# STC12C5A60S2.net
KiCad netlist of a schematic drawn in Altium Designer
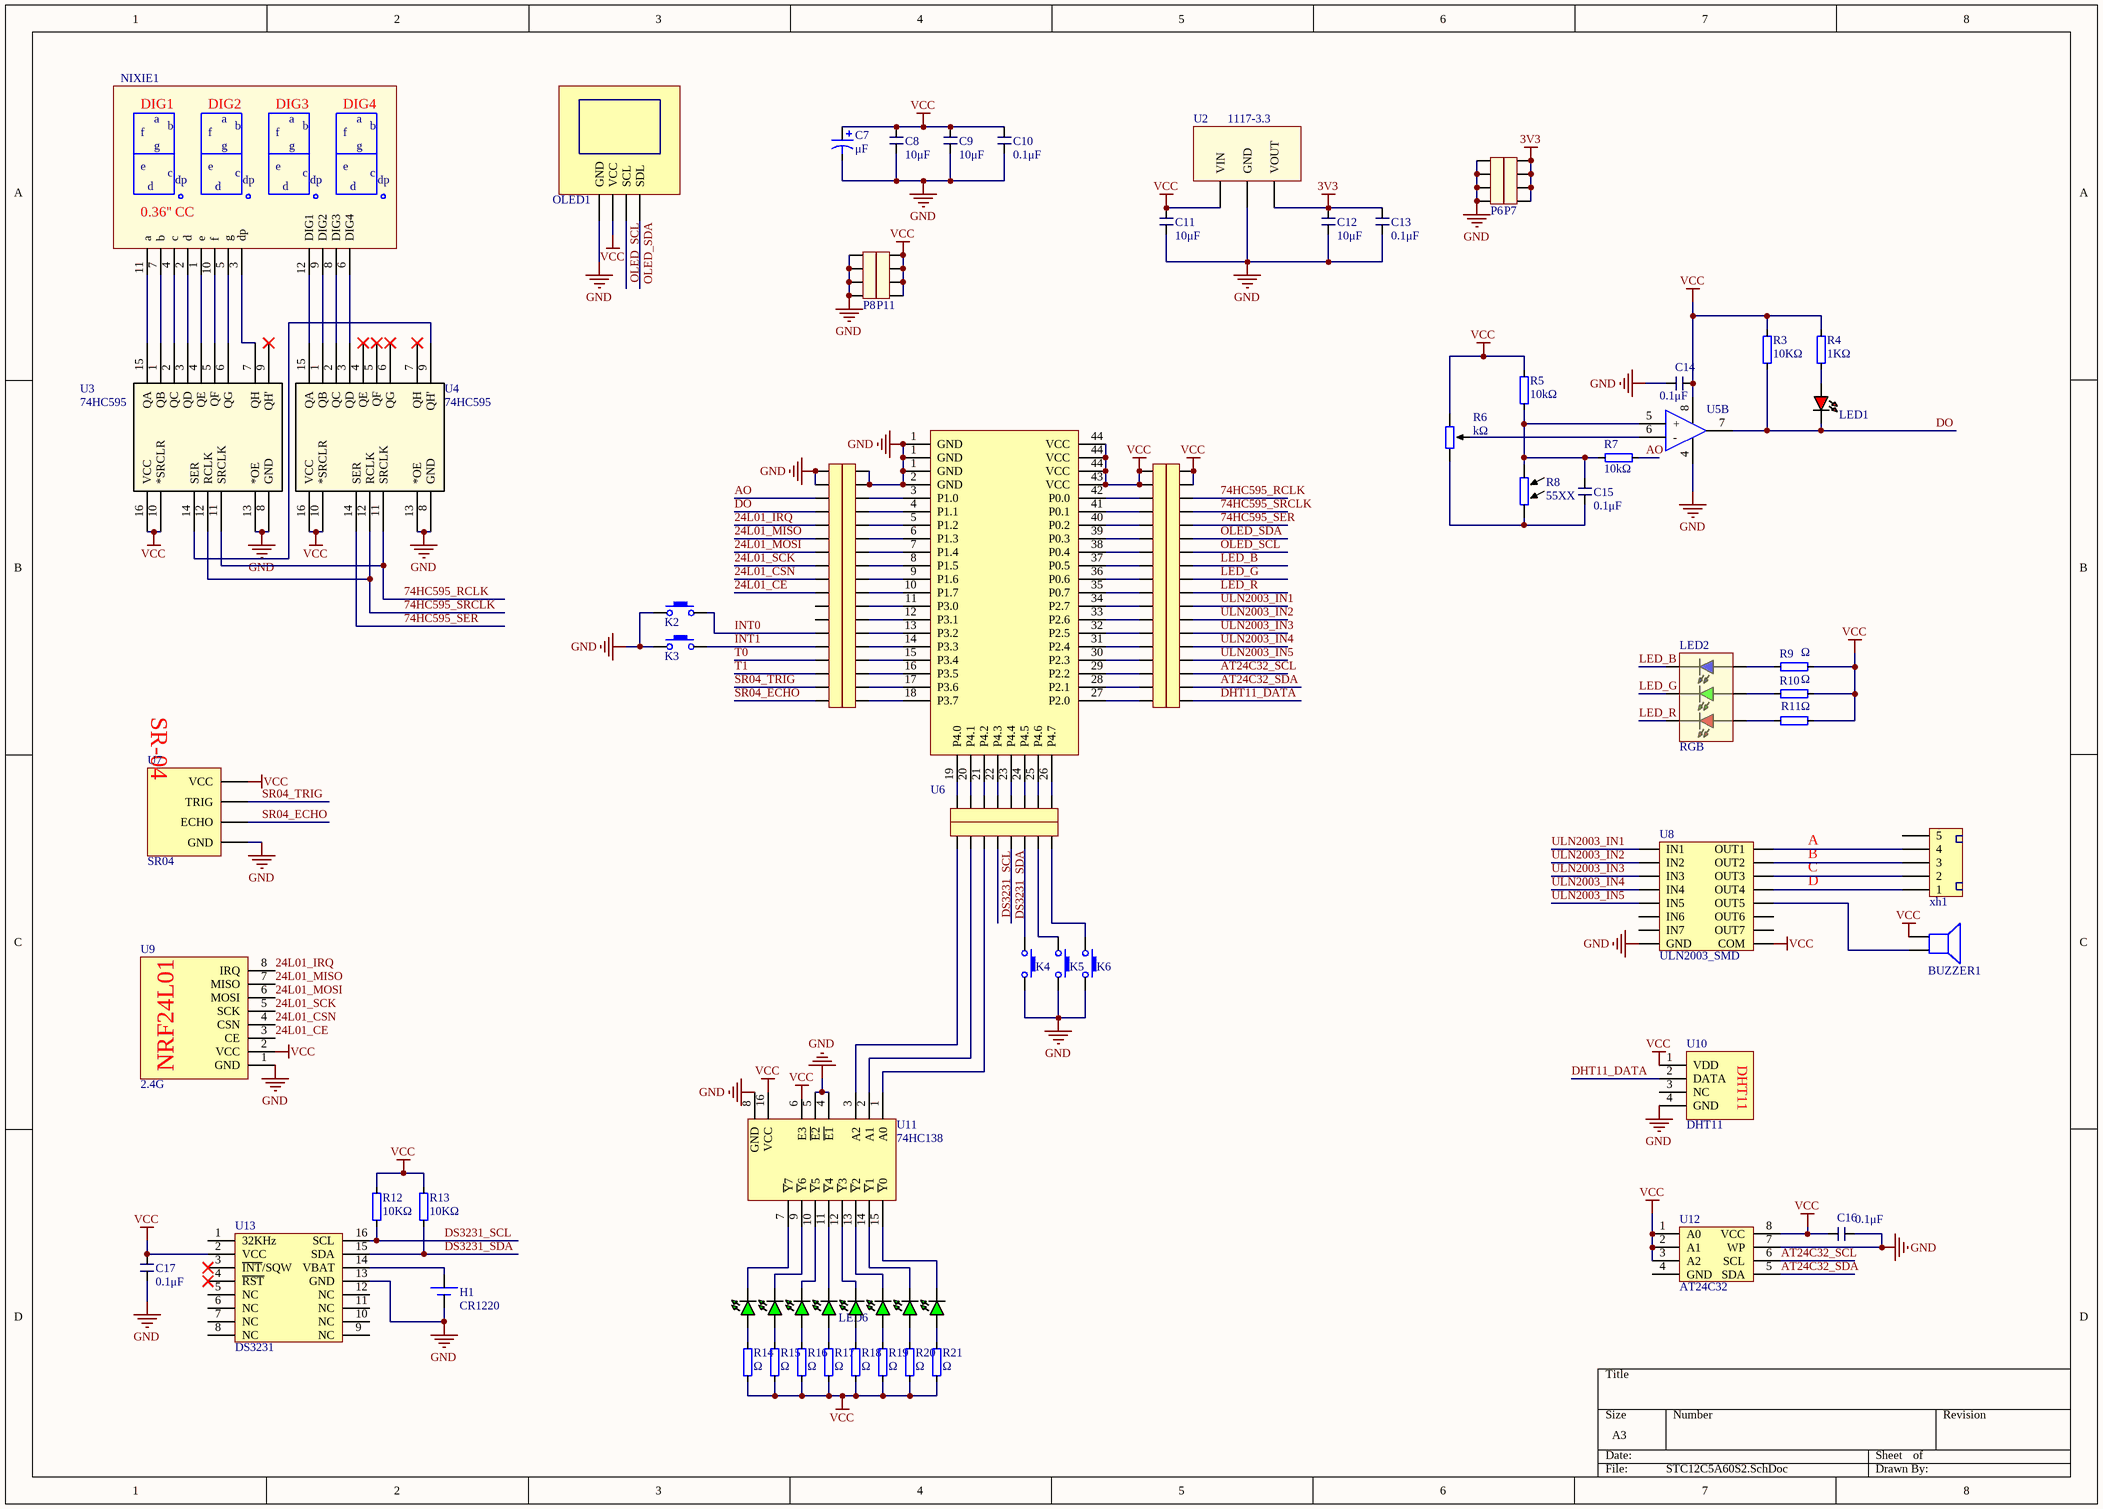
[diagram p0: STC12C5A60S2.SchDoc]

(export (version "E")
  (design (tool "Eeschema 10.0.6"))
  (components
    (comp (ref "BUZZER1")
      (value "BUZZER 9.6X5.5_4MM")
      (footprint "BUZZER9.6x4_4mm")
      (libsource (lib "节能库") (part "BUZZER 9.6X5.5_4MM"))
    )
    (comp (ref "C7") (value "μF") (footprint "TAC_C") (libsource (lib "节能库") (part "C_TAC-C")))
    (comp (ref "C8") (value "10μF") (footprint "C_0805") (libsource (lib "节能库") (part "C_0805")))
    (comp (ref "C9") (value "10μF") (footprint "C_0805") (libsource (lib "节能库") (part "C_0805")))
    (comp (ref "C10") (value "0.1μF") (footprint "C_0805") (libsource (lib "节能库") (part "C_0805")))
    (comp (ref "C11") (value "10μF") (footprint "C_0805") (libsource (lib "节能库") (part "C_0805")))
    (comp (ref "C12") (value "10μF") (footprint "C_0805") (libsource (lib "节能库") (part "C_0805")))
    (comp (ref "C13") (value "0.1μF") (footprint "C_0805") (libsource (lib "节能库") (part "C_0805")))
    (comp (ref "C14") (value "0.1μF") (footprint "C_0805") (libsource (lib "节能库") (part "C_0805")))
    (comp (ref "C15") (value "0.1μF") (footprint "C_0805") (libsource (lib "节能库") (part "C_0805")))
    (comp (ref "C16") (value "0.1μF") (footprint "C_0805") (libsource (lib "节能库") (part "C_0805")))
    (comp (ref "C17") (value "0.1μF") (footprint "C_0805") (libsource (lib "节能库") (part "C_0805")))
    (comp (ref "H1")
      (value "CR1220")
      (footprint "holder_CR1220_SMD")
      (libsource (lib "节能库") (part "holder_CR1220_SMD"))
    )
    (comp (ref "K2")
      (value "TACT SWITCH_4_DIP")
      (footprint "TACT SWITCH_4_DIP")
      (libsource (lib "") (part "TACT SWITCH_4_DIP_1"))
    )
    (comp (ref "K3")
      (value "TACT SWITCH_4_DIP")
      (footprint "TACT SWITCH_4_DIP")
      (libsource (lib "") (part "TACT SWITCH_4_DIP_1"))
    )
    (comp (ref "K4")
      (value "TACT SWITCH_4_DIP")
      (footprint "TACT SWITCH_4_DIP")
      (libsource (lib "节能库") (part "TACT SWITCH_4_DIP"))
    )
    (comp (ref "K5")
      (value "TACT SWITCH_4_DIP")
      (footprint "TACT SWITCH_4_DIP")
      (libsource (lib "节能库") (part "TACT SWITCH_4_DIP"))
    )
    (comp (ref "K6")
      (value "TACT SWITCH_4_DIP")
      (footprint "TACT SWITCH_4_DIP")
      (libsource (lib "节能库") (part "TACT SWITCH_4_DIP"))
    )
    (comp (ref "LED1")
      (value "LED_0603-R")
      (footprint "LED_0603-R")
      (libsource (lib "节能库") (part "LED_0603-R"))
    )
    (comp (ref "LED2") (value "RGB") (footprint "LED 5050_RGB") (libsource (lib "节能库") (part "LED_5050_RGB")))
    (comp (ref "LED3")
      (value "LED_0603-G")
      (footprint "LED_0603-G")
      (libsource (lib "节能库") (part "LED_0603-G"))
    )
    (comp (ref "LED4")
      (value "LED_0603-G")
      (footprint "LED_0603-G")
      (libsource (lib "节能库") (part "LED_0603-G"))
    )
    (comp (ref "LED5")
      (value "LED_0603-G")
      (footprint "LED_0603-G")
      (libsource (lib "节能库") (part "LED_0603-G"))
    )
    (comp (ref "LED6")
      (value "LED_0603-G")
      (footprint "LED_0603-G")
      (libsource (lib "节能库") (part "LED_0603-G"))
    )
    (comp (ref "LED7")
      (value "LED_0603-G")
      (footprint "LED_0603-G")
      (libsource (lib "节能库") (part "LED_0603-G"))
    )
    (comp (ref "LED8")
      (value "LED_0603-G")
      (footprint "LED_0603-G")
      (libsource (lib "节能库") (part "LED_0603-G"))
    )
    (comp (ref "LED9")
      (value "LED_0603-G")
      (footprint "LED_0603-G")
      (libsource (lib "节能库") (part "LED_0603-G"))
    )
    (comp (ref "LED10")
      (value "LED_0603-G")
      (footprint "LED_0603-G")
      (libsource (lib "节能库") (part "LED_0603-G"))
    )
    (comp (ref "NIXIE1")
      (value "Nixie Tube_CC(0.36in)_4")
      (footprint "Nixie Tube_4(0.36in)")
      (libsource (lib "节能库") (part "Nixie Tube_CC(0.36in)_4"))
    )
    (comp (ref "OLED1")
      (value "0.96''")
      (footprint "OLED 0.96''")
      (libsource (lib "节能库") (part "OLED 0.96''_module"))
    )
    (comp (ref "P6") (value "PIN4") (footprint "PIN_4") (libsource (lib "") (part "PIN4_1")))
    (comp (ref "P7") (value "PIN4") (footprint "PIN_4") (libsource (lib "节能库") (part "PIN4")))
    (comp (ref "P8") (value "PIN4") (footprint "PIN_4") (libsource (lib "") (part "PIN4_1")))
    (comp (ref "P11") (value "PIN4") (footprint "PIN_4") (libsource (lib "节能库") (part "PIN4")))
    (comp (ref "P12") (value "PIN8") (footprint "PIN_8") (libsource (lib "") (part "PIN8_1")))
    (comp (ref "P13") (value "PIN8") (footprint "PIN_8") (libsource (lib "节能库") (part "PIN8")))
    (comp (ref "PIN1") (value "PIN18") (footprint "PIN_18") (libsource (lib "") (part "PIN18_1")))
    (comp (ref "PIN2") (value "PIN18") (footprint "PIN_18") (libsource (lib "节能库") (part "PIN18")))
    (comp (ref "PIN3") (value "PIN18") (footprint "PIN_18") (libsource (lib "") (part "PIN18_1")))
    (comp (ref "PIN4") (value "PIN18") (footprint "PIN_18") (libsource (lib "节能库") (part "PIN18")))
    (comp (ref "R3") (value "10KΩ") (footprint "R_0805") (libsource (lib "节能库") (part "R_0805")))
    (comp (ref "R4") (value "1KΩ") (footprint "R_0805") (libsource (lib "节能库") (part "R_0805")))
    (comp (ref "R5") (value "10kΩ") (footprint "R_0805") (libsource (lib "节能库") (part "R_0805")))
    (comp (ref "R6") (value "kΩ") (footprint "RP_3362P") (libsource (lib "节能库") (part "RP_3362P")))
    (comp (ref "R7") (value "10kΩ") (footprint "R_0805") (libsource (lib "节能库") (part "R_0805")))
    (comp (ref "R8") (value "55XX") (footprint "GM55-55XX") (libsource (lib "节能库") (part "GM55-55XX")))
    (comp (ref "R9") (value "Ω") (footprint "R_0805") (libsource (lib "节能库") (part "R_0805")))
    (comp (ref "R10") (value "Ω") (footprint "R_0805") (libsource (lib "节能库") (part "R_0805")))
    (comp (ref "R11") (value "Ω") (footprint "R_0805") (libsource (lib "节能库") (part "R_0805")))
    (comp (ref "R12") (value "10KΩ") (footprint "R_0805") (libsource (lib "节能库") (part "R_0805")))
    (comp (ref "R13") (value "10KΩ") (footprint "R_0805") (libsource (lib "节能库") (part "R_0805")))
    (comp (ref "R14") (value "Ω") (footprint "R_0805") (libsource (lib "节能库") (part "R_0805")))
    (comp (ref "R15") (value "Ω") (footprint "R_0805") (libsource (lib "节能库") (part "R_0805")))
    (comp (ref "R16") (value "Ω") (footprint "R_0805") (libsource (lib "节能库") (part "R_0805")))
    (comp (ref "R17") (value "Ω") (footprint "R_0805") (libsource (lib "节能库") (part "R_0805")))
    (comp (ref "R18") (value "Ω") (footprint "R_0805") (libsource (lib "节能库") (part "R_0805")))
    (comp (ref "R19") (value "Ω") (footprint "R_0805") (libsource (lib "节能库") (part "R_0805")))
    (comp (ref "R20") (value "Ω") (footprint "R_0805") (libsource (lib "节能库") (part "R_0805")))
    (comp (ref "R21") (value "Ω") (footprint "R_0805") (libsource (lib "节能库") (part "R_0805")))
    (comp (ref "U2") (value "1117-3.3") (footprint "SOT_223") (libsource (lib "节能库") (part "AMS1117-3.3")))
    (comp (ref "U3") (value "74HC595") (footprint "SOP_16") (libsource (lib "节能库") (part "74HC595")))
    (comp (ref "U4") (value "74HC595") (footprint "SOP_16") (libsource (lib "节能库") (part "74HC595")))
    (comp (ref "U5") (value "LM393_DIP") (footprint "SOP_8") (libsource (lib "节能库") (part "LM393_DIP")))
    (comp (ref "U6")
      (value "socket")
      (footprint "STC12_moudle")
      (libsource (lib "节能库") (part "STC12C_module"))
    )
    (comp (ref "U7") (value "SR04") (footprint "SR04") (libsource (lib "节能库") (part "SR04")))
    (comp (ref "U8") (value "ULN2003_SMD") (footprint "SOP_16") (libsource (lib "节能库") (part "ULN2003_SMD")))
    (comp (ref "U9") (value "2.4G") (footprint "NRF24L01") (libsource (lib "节能库") (part "NRF24L01")))
    (comp (ref "U10") (value "DHT11") (footprint "DHT11") (libsource (lib "节能库") (part "DHT11")))
    (comp (ref "U11") (value "74HC138") (footprint "SOP_16") (libsource (lib "节能库") (part "74HC138")))
    (comp (ref "U12") (value "AT24C32") (footprint "SOP_8") (libsource (lib "节能库") (part "AT24C32")))
    (comp (ref "U13") (value "DS3231") (footprint "SOP_16") (libsource (lib "节能库") (part "DS3231_SOP16")))
    (comp (ref "xh1") (value "XH2.54_5") (footprint "XH2.54_5") (libsource (lib "节能库") (part "XH2.54_5")))
  )
  (nets
    (net (code "1") (name "/24L01_CE") (class "Default")
      (node (ref "PIN1") (pin "9") (pinfunction "9_9") (pintype "passive"))
      (node (ref "U9") (pin "3") (pinfunction "CE_3") (pintype "passive"))
    )
    (net (code "2") (name "/24L01_CSN") (class "Default")
      (node (ref "PIN1") (pin "10") (pinfunction "10_10") (pintype "passive"))
      (node (ref "U9") (pin "4") (pinfunction "CSN_4") (pintype "passive"))
    )
    (net (code "3") (name "/24L01_IRQ") (class "Default")
      (node (ref "PIN1") (pin "14") (pinfunction "14_14") (pintype "passive"))
      (node (ref "U9") (pin "8") (pinfunction "IRQ_8") (pintype "passive"))
    )
    (net (code "4") (name "/24L01_MISO") (class "Default")
      (node (ref "PIN1") (pin "13") (pinfunction "13_13") (pintype "passive"))
      (node (ref "U9") (pin "7") (pinfunction "MISO_7") (pintype "passive"))
    )
    (net (code "5") (name "/24L01_MOSI") (class "Default")
      (node (ref "PIN1") (pin "12") (pinfunction "12_12") (pintype "passive"))
      (node (ref "U9") (pin "6") (pinfunction "MOSI_6") (pintype "passive"))
    )
    (net (code "6") (name "/24L01_SCK") (class "Default")
      (node (ref "PIN1") (pin "11") (pinfunction "11_11") (pintype "passive"))
      (node (ref "U9") (pin "5") (pinfunction "SCK_5") (pintype "passive"))
    )
    (net (code "7") (name "/74HC595_RCLK") (class "Default")
      (node (ref "PIN4") (pin "16") (pinfunction "16_16") (pintype "passive"))
      (node (ref "U3") (pin "11") (pinfunction "SRCLK_11") (pintype "passive"))
      (node (ref "U4") (pin "11") (pinfunction "SRCLK_11") (pintype "passive"))
    )
    (net (code "8") (name "/74HC595_SER") (class "Default")
      (node (ref "PIN4") (pin "14") (pinfunction "14_14") (pintype "passive"))
      (node (ref "U4") (pin "14") (pinfunction "SER_14") (pintype "passive"))
    )
    (net (code "9") (name "/74HC595_SRCLK") (class "Default")
      (node (ref "PIN4") (pin "15") (pinfunction "15_15") (pintype "passive"))
      (node (ref "U3") (pin "12") (pinfunction "RCLK_12") (pintype "passive"))
      (node (ref "U4") (pin "12") (pinfunction "RCLK_12") (pintype "passive"))
    )
    (net (code "10") (name "/AO") (class "Default")
      (node (ref "PIN1") (pin "16") (pinfunction "16_16") (pintype "passive"))
      (node (ref "R7") (pin "2") (pintype "passive"))
    )
    (net (code "11") (name "/AT24C32_SCL") (class "Default")
      (node (ref "PIN4") (pin "3") (pinfunction "3_3") (pintype "passive"))
      (node (ref "U12") (pin "6") (pinfunction "SCL_6") (pintype "passive"))
    )
    (net (code "12") (name "/AT24C32_SDA") (class "Default")
      (node (ref "PIN4") (pin "2") (pinfunction "2_2") (pintype "passive"))
      (node (ref "U12") (pin "5") (pinfunction "SDA_5") (pintype "passive"))
    )
    (net (code "13") (name "/DHT11_DATA") (class "Default")
      (node (ref "PIN4") (pin "1") (pinfunction "1_1") (pintype "passive"))
      (node (ref "U10") (pin "2") (pinfunction "DATA_2") (pintype "passive"))
    )
    (net (code "14") (name "/DO") (class "Default")
      (node (ref "LED1") (pin "2") (pinfunction "2_2") (pintype "passive"))
      (node (ref "PIN1") (pin "15") (pinfunction "15_15") (pintype "passive"))
      (node (ref "R3") (pin "1") (pintype "passive"))
      (node (ref "U5") (pin "7") (pintype "passive"))
    )
    (net (code "15") (name "/DS3231_SCL") (class "Default")
      (node (ref "P13") (pin "4") (pinfunction "4_4") (pintype "passive"))
      (node (ref "R12") (pin "1") (pintype "passive"))
      (node (ref "U13") (pin "16") (pinfunction "SCL_16") (pintype "passive"))
    )
    (net (code "16") (name "/DS3231_SDA") (class "Default")
      (node (ref "P13") (pin "5") (pinfunction "5_5") (pintype "passive"))
      (node (ref "R13") (pin "1") (pintype "passive"))
      (node (ref "U13") (pin "15") (pinfunction "SDA_15") (pintype "passive"))
    )
    (net (code "17") (name "/INT0") (class "Default")
      (node (ref "K2") (pin "2") (pinfunction "2_2") (pintype "passive"))
      (node (ref "PIN1") (pin "6") (pinfunction "6_6") (pintype "passive"))
    )
    (net (code "18") (name "/INT1") (class "Default")
      (node (ref "K3") (pin "2") (pinfunction "2_2") (pintype "passive"))
      (node (ref "PIN1") (pin "5") (pinfunction "5_5") (pintype "passive"))
    )
    (net (code "19") (name "/LED_B") (class "Default")
      (node (ref "LED2") (pin "1") (pinfunction "1_1") (pintype "passive"))
      (node (ref "PIN4") (pin "11") (pinfunction "11_11") (pintype "passive"))
    )
    (net (code "20") (name "/LED_G") (class "Default")
      (node (ref "LED2") (pin "5") (pinfunction "5_5") (pintype "passive"))
      (node (ref "PIN4") (pin "10") (pinfunction "10_10") (pintype "passive"))
    )
    (net (code "21") (name "/LED_R") (class "Default")
      (node (ref "LED2") (pin "3") (pinfunction "3_3") (pintype "passive"))
      (node (ref "PIN4") (pin "9") (pinfunction "9_9") (pintype "passive"))
    )
    (net (code "22") (name "/OLED_SCL") (class "Default")
      (node (ref "OLED1") (pin "3") (pinfunction "SCL_3") (pintype "passive"))
      (node (ref "PIN4") (pin "12") (pinfunction "12_12") (pintype "passive"))
    )
    (net (code "23") (name "/OLED_SDA") (class "Default")
      (node (ref "OLED1") (pin "4") (pinfunction "SDL_4") (pintype "passive"))
      (node (ref "PIN4") (pin "13") (pinfunction "13_13") (pintype "passive"))
    )
    (net (code "24") (name "/SR04_ECHO") (class "Default")
      (node (ref "PIN1") (pin "1") (pinfunction "1_1") (pintype "passive"))
      (node (ref "U7") (pin "3") (pinfunction "ECHO_3") (pintype "passive"))
    )
    (net (code "25") (name "/SR04_TRIG") (class "Default")
      (node (ref "PIN1") (pin "2") (pinfunction "2_2") (pintype "passive"))
      (node (ref "U7") (pin "2") (pinfunction "TRIG_2") (pintype "passive"))
    )
    (net (code "26") (name "/T0") (class "Default")
      (node (ref "PIN1") (pin "4") (pinfunction "4_4") (pintype "passive"))
    )
    (net (code "27") (name "/T1") (class "Default")
      (node (ref "PIN1") (pin "3") (pinfunction "3_3") (pintype "passive"))
    )
    (net (code "28") (name "/ULN2003_IN1") (class "Default")
      (node (ref "PIN4") (pin "8") (pinfunction "8_8") (pintype "passive"))
      (node (ref "U8") (pin "1") (pinfunction "IN1_1") (pintype "passive"))
    )
    (net (code "29") (name "/ULN2003_IN2") (class "Default")
      (node (ref "PIN4") (pin "7") (pinfunction "7_7") (pintype "passive"))
      (node (ref "U8") (pin "2") (pinfunction "IN2_2") (pintype "passive"))
    )
    (net (code "30") (name "/ULN2003_IN3") (class "Default")
      (node (ref "PIN4") (pin "6") (pinfunction "6_6") (pintype "passive"))
      (node (ref "U8") (pin "3") (pinfunction "IN3_3") (pintype "passive"))
    )
    (net (code "31") (name "/ULN2003_IN4") (class "Default")
      (node (ref "PIN4") (pin "5") (pinfunction "5_5") (pintype "passive"))
      (node (ref "U8") (pin "4") (pinfunction "IN4_4") (pintype "passive"))
    )
    (net (code "32") (name "/ULN2003_IN5") (class "Default")
      (node (ref "PIN4") (pin "4") (pinfunction "4_4") (pintype "passive"))
      (node (ref "U8") (pin "5") (pinfunction "IN5_5") (pintype "passive"))
    )
    (net (code "33") (name "3V3") (class "Default")
      (node (ref "C12") (pin "1") (pinfunction "1_1") (pintype "passive"))
      (node (ref "C13") (pin "1") (pinfunction "1_1") (pintype "passive"))
      (node (ref "P7") (pin "1") (pinfunction "1_1") (pintype "passive"))
      (node (ref "P7") (pin "2") (pinfunction "2_2") (pintype "passive"))
      (node (ref "P7") (pin "3") (pinfunction "3_3") (pintype "passive"))
      (node (ref "P7") (pin "4") (pinfunction "4_4") (pintype "passive"))
      (node (ref "U2") (pin "2") (pinfunction "VOUT_2") (pintype "passive"))
    )
    (net (code "34") (name "GND") (class "Default")
      (node (ref "C10") (pin "2") (pinfunction "2_2") (pintype "passive"))
      (node (ref "C11") (pin "2") (pinfunction "2_2") (pintype "passive"))
      (node (ref "C12") (pin "2") (pinfunction "2_2") (pintype "passive"))
      (node (ref "C13") (pin "2") (pinfunction "2_2") (pintype "passive"))
      (node (ref "C14") (pin "1") (pinfunction "1_1") (pintype "passive"))
      (node (ref "C16") (pin "2") (pinfunction "2_2") (pintype "passive"))
      (node (ref "C17") (pin "2") (pinfunction "2_2") (pintype "passive"))
      (node (ref "C7") (pin "2") (pinfunction "2_2") (pintype "passive"))
      (node (ref "C8") (pin "2") (pinfunction "2_2") (pintype "passive"))
      (node (ref "C9") (pin "2") (pinfunction "2_2") (pintype "passive"))
      (node (ref "H1") (pin "2") (pinfunction "-_2") (pintype "passive"))
      (node (ref "K2") (pin "1") (pinfunction "1_1") (pintype "passive"))
      (node (ref "K3") (pin "1") (pinfunction "1_1") (pintype "passive"))
      (node (ref "K4") (pin "2") (pinfunction "2_2") (pintype "passive"))
      (node (ref "K5") (pin "2") (pinfunction "2_2") (pintype "passive"))
      (node (ref "K6") (pin "2") (pinfunction "2_2") (pintype "passive"))
      (node (ref "OLED1") (pin "1") (pinfunction "GND_1") (pintype "passive"))
      (node (ref "P6") (pin "1") (pinfunction "1_1") (pintype "passive"))
      (node (ref "P6") (pin "2") (pinfunction "2_2") (pintype "passive"))
      (node (ref "P6") (pin "3") (pinfunction "3_3") (pintype "passive"))
      (node (ref "P6") (pin "4") (pinfunction "4_4") (pintype "passive"))
      (node (ref "P8") (pin "1") (pinfunction "1_1") (pintype "passive"))
      (node (ref "P8") (pin "2") (pinfunction "2_2") (pintype "passive"))
      (node (ref "P8") (pin "3") (pinfunction "3_3") (pintype "passive"))
      (node (ref "P8") (pin "4") (pinfunction "4_4") (pintype "passive"))
      (node (ref "PIN1") (pin "17") (pinfunction "17_17") (pintype "passive"))
      (node (ref "PIN1") (pin "18") (pinfunction "18_18") (pintype "passive"))
      (node (ref "PIN2") (pin "17") (pinfunction "17_17") (pintype "passive"))
      (node (ref "PIN2") (pin "18") (pinfunction "18_18") (pintype "passive"))
      (node (ref "U10") (pin "4") (pinfunction "GND_4") (pintype "passive"))
      (node (ref "U11") (pin "4") (pinfunction "~{E1}_4") (pintype "passive"))
      (node (ref "U11") (pin "5") (pinfunction "~{E2}_5") (pintype "passive"))
      (node (ref "U11") (pin "8") (pinfunction "GND_8") (pintype "passive"))
      (node (ref "U12") (pin "7") (pinfunction "WP_7") (pintype "passive"))
      (node (ref "U13") (pin "13") (pinfunction "GND_13") (pintype "passive"))
      (node (ref "U2") (pin "1") (pinfunction "GND_1") (pintype "passive"))
      (node (ref "U3") (pin "13") (pinfunction "*OE_13") (pintype "passive"))
      (node (ref "U3") (pin "8") (pinfunction "GND_8") (pintype "passive"))
      (node (ref "U4") (pin "13") (pinfunction "*OE_13") (pintype "passive"))
      (node (ref "U4") (pin "8") (pinfunction "GND_8") (pintype "passive"))
      (node (ref "U5") (pin "4") (pinfunction "GND_4") (pintype "passive"))
      (node (ref "U6") (pin "1") (pinfunction "GND_1") (pintype "passive"))
      (node (ref "U6") (pin "2") (pinfunction "GND_2") (pintype "passive"))
      (node (ref "U7") (pin "4") (pinfunction "GND_4") (pintype "passive"))
      (node (ref "U8") (pin "8") (pinfunction "GND_8") (pintype "passive"))
      (node (ref "U9") (pin "1") (pinfunction "GND_1") (pintype "passive"))
    )
    (net (code "35") (name "Net-(C15-Pad2)") (class "Default")
      (node (ref "C15") (pin "2") (pinfunction "2_2") (pintype "passive"))
      (node (ref "R6") (pin "3") (pinfunction "3_3") (pintype "passive"))
      (node (ref "R8") (pin "2") (pintype "passive"))
    )
    (net (code "36") (name "Net-(H1-+)") (class "Default")
      (node (ref "H1") (pin "1") (pinfunction "+_1") (pintype "passive"))
      (node (ref "U13") (pin "14") (pinfunction "VBAT_14") (pintype "passive"))
    )
    (net (code "37") (name "Net-(K4-Pad1)") (class "Default")
      (node (ref "K4") (pin "1") (pinfunction "1_1") (pintype "passive"))
      (node (ref "P13") (pin "6") (pinfunction "6_6") (pintype "passive"))
    )
    (net (code "38") (name "Net-(K5-Pad1)") (class "Default")
      (node (ref "K5") (pin "1") (pinfunction "1_1") (pintype "passive"))
      (node (ref "P13") (pin "7") (pinfunction "7_7") (pintype "passive"))
    )
    (net (code "39") (name "Net-(K6-Pad1)") (class "Default")
      (node (ref "K6") (pin "1") (pinfunction "1_1") (pintype "passive"))
      (node (ref "P13") (pin "8") (pinfunction "8_8") (pintype "passive"))
    )
    (net (code "40") (name "Net-(LED1-Pad1)") (class "Default")
      (node (ref "LED1") (pin "1") (pinfunction "1_1") (pintype "passive"))
      (node (ref "R4") (pin "1") (pintype "passive"))
    )
    (net (code "41") (name "Net-(LED2-Pad2)") (class "Default")
      (node (ref "LED2") (pin "2") (pinfunction "2_2") (pintype "passive"))
      (node (ref "R9") (pin "1") (pintype "passive"))
    )
    (net (code "42") (name "Net-(LED2-Pad4)") (class "Default")
      (node (ref "LED2") (pin "4") (pinfunction "4_4") (pintype "passive"))
      (node (ref "R11") (pin "1") (pintype "passive"))
    )
    (net (code "43") (name "Net-(LED2-Pad6)") (class "Default")
      (node (ref "LED2") (pin "6") (pinfunction "6_6") (pintype "passive"))
      (node (ref "R10") (pin "1") (pintype "passive"))
    )
    (net (code "44") (name "Net-(LED3-Pad1)") (class "Default")
      (node (ref "LED3") (pin "1") (pinfunction "1_1") (pintype "passive"))
      (node (ref "R14") (pin "2") (pintype "passive"))
    )
    (net (code "45") (name "Net-(LED4-Pad1)") (class "Default")
      (node (ref "LED4") (pin "1") (pinfunction "1_1") (pintype "passive"))
      (node (ref "R15") (pin "2") (pintype "passive"))
    )
    (net (code "46") (name "Net-(LED5-Pad1)") (class "Default")
      (node (ref "LED5") (pin "1") (pinfunction "1_1") (pintype "passive"))
      (node (ref "R16") (pin "2") (pintype "passive"))
    )
    (net (code "47") (name "Net-(LED6-Pad1)") (class "Default")
      (node (ref "LED6") (pin "1") (pinfunction "1_1") (pintype "passive"))
      (node (ref "R17") (pin "2") (pintype "passive"))
    )
    (net (code "48") (name "Net-(LED7-Pad1)") (class "Default")
      (node (ref "LED7") (pin "1") (pinfunction "1_1") (pintype "passive"))
      (node (ref "R18") (pin "2") (pintype "passive"))
    )
    (net (code "49") (name "Net-(LED8-Pad1)") (class "Default")
      (node (ref "LED8") (pin "1") (pinfunction "1_1") (pintype "passive"))
      (node (ref "R19") (pin "2") (pintype "passive"))
    )
    (net (code "50") (name "Net-(LED9-Pad1)") (class "Default")
      (node (ref "LED9") (pin "1") (pinfunction "1_1") (pintype "passive"))
      (node (ref "R20") (pin "2") (pintype "passive"))
    )
    (net (code "51") (name "Net-(LED10-Pad1)") (class "Default")
      (node (ref "LED10") (pin "1") (pinfunction "1_1") (pintype "passive"))
      (node (ref "R21") (pin "2") (pintype "passive"))
    )
    (net (code "52") (name "Net-(NIXIE1-DIG1)") (class "Default")
      (node (ref "NIXIE1") (pin "12") (pinfunction "DIG1_12") (pintype "passive"))
      (node (ref "U4") (pin "15") (pinfunction "QA_15") (pintype "passive"))
    )
    (net (code "53") (name "Net-(NIXIE1-DIG2)") (class "Default")
      (node (ref "NIXIE1") (pin "9") (pinfunction "DIG2_9") (pintype "passive"))
      (node (ref "U4") (pin "1") (pinfunction "QB_1") (pintype "passive"))
    )
    (net (code "54") (name "Net-(NIXIE1-DIG3)") (class "Default")
      (node (ref "NIXIE1") (pin "8") (pinfunction "DIG3_8") (pintype "passive"))
      (node (ref "U4") (pin "2") (pinfunction "QC_2") (pintype "passive"))
    )
    (net (code "55") (name "Net-(NIXIE1-DIG4)") (class "Default")
      (node (ref "NIXIE1") (pin "6") (pinfunction "DIG4_6") (pintype "passive"))
      (node (ref "U4") (pin "3") (pinfunction "QD_3") (pintype "passive"))
    )
    (net (code "56") (name "Net-(NIXIE1-a)") (class "Default")
      (node (ref "NIXIE1") (pin "11") (pinfunction "a_11") (pintype "passive"))
      (node (ref "U3") (pin "15") (pinfunction "QA_15") (pintype "passive"))
    )
    (net (code "57") (name "Net-(NIXIE1-b)") (class "Default")
      (node (ref "NIXIE1") (pin "7") (pinfunction "b_7") (pintype "passive"))
      (node (ref "U3") (pin "1") (pinfunction "QB_1") (pintype "passive"))
    )
    (net (code "58") (name "Net-(NIXIE1-c)") (class "Default")
      (node (ref "NIXIE1") (pin "4") (pinfunction "c_4") (pintype "passive"))
      (node (ref "U3") (pin "2") (pinfunction "QC_2") (pintype "passive"))
    )
    (net (code "59") (name "Net-(NIXIE1-d)") (class "Default")
      (node (ref "NIXIE1") (pin "2") (pinfunction "d_2") (pintype "passive"))
      (node (ref "U3") (pin "3") (pinfunction "QD_3") (pintype "passive"))
    )
    (net (code "60") (name "Net-(NIXIE1-dp)") (class "Default")
      (node (ref "NIXIE1") (pin "3") (pinfunction "dp_3") (pintype "passive"))
      (node (ref "U3") (pin "7") (pinfunction "QH_7") (pintype "passive"))
    )
    (net (code "61") (name "Net-(NIXIE1-e)") (class "Default")
      (node (ref "NIXIE1") (pin "1") (pinfunction "e_1") (pintype "passive"))
      (node (ref "U3") (pin "4") (pinfunction "QE_4") (pintype "passive"))
    )
    (net (code "62") (name "Net-(NIXIE1-f)") (class "Default")
      (node (ref "NIXIE1") (pin "10") (pinfunction "f_10") (pintype "passive"))
      (node (ref "U3") (pin "5") (pinfunction "QF_5") (pintype "passive"))
    )
    (net (code "63") (name "Net-(NIXIE1-g)") (class "Default")
      (node (ref "NIXIE1") (pin "5") (pinfunction "g_5") (pintype "passive"))
      (node (ref "U3") (pin "6") (pinfunction "QG_6") (pintype "passive"))
    )
    (net (code "64") (name "Net-(U3-SER)") (class "Default")
      (node (ref "U3") (pin "14") (pinfunction "SER_14") (pintype "passive"))
      (node (ref "U4") (pin "9") (pinfunction "QH'_9") (pintype "passive"))
    )
    (net (code "65") (name "Net-(U5B-+)") (class "Default")
      (node (ref "C15") (pin "1") (pinfunction "1_1") (pintype "passive"))
      (node (ref "R5") (pin "2") (pintype "passive"))
      (node (ref "R7") (pin "1") (pintype "passive"))
      (node (ref "R8") (pin "1") (pintype "passive"))
      (node (ref "U5") (pin "5") (pinfunction "+_5") (pintype "passive"))
    )
    (net (code "66") (name "Net-(U5B--)") (class "Default")
      (node (ref "R6") (pin "2") (pinfunction "2_2") (pintype "passive"))
      (node (ref "U5") (pin "6") (pinfunction "-_6") (pintype "passive"))
    )
    (net (code "67") (name "Net-(U6-P0.0)") (class "Default")
      (node (ref "PIN3") (pin "16") (pinfunction "16_16") (pintype "passive"))
      (node (ref "U6") (pin "42") (pinfunction "P0.0_42") (pintype "passive"))
    )
    (net (code "68") (name "Net-(U6-P0.1)") (class "Default")
      (node (ref "PIN3") (pin "15") (pinfunction "15_15") (pintype "passive"))
      (node (ref "U6") (pin "41") (pinfunction "P0.1_41") (pintype "passive"))
    )
    (net (code "69") (name "Net-(U6-P0.2)") (class "Default")
      (node (ref "PIN3") (pin "14") (pinfunction "14_14") (pintype "passive"))
      (node (ref "U6") (pin "40") (pinfunction "P0.2_40") (pintype "passive"))
    )
    (net (code "70") (name "Net-(U6-P0.3)") (class "Default")
      (node (ref "PIN3") (pin "13") (pinfunction "13_13") (pintype "passive"))
      (node (ref "U6") (pin "39") (pinfunction "P0.3_39") (pintype "passive"))
    )
    (net (code "71") (name "Net-(U6-P0.4)") (class "Default")
      (node (ref "PIN3") (pin "12") (pinfunction "12_12") (pintype "passive"))
      (node (ref "U6") (pin "38") (pinfunction "P0.4_38") (pintype "passive"))
    )
    (net (code "72") (name "Net-(U6-P0.5)") (class "Default")
      (node (ref "PIN3") (pin "11") (pinfunction "11_11") (pintype "passive"))
      (node (ref "U6") (pin "37") (pinfunction "P0.5_37") (pintype "passive"))
    )
    (net (code "73") (name "Net-(U6-P0.6)") (class "Default")
      (node (ref "PIN3") (pin "10") (pinfunction "10_10") (pintype "passive"))
      (node (ref "U6") (pin "36") (pinfunction "P0.6_36") (pintype "passive"))
    )
    (net (code "74") (name "Net-(U6-P0.7)") (class "Default")
      (node (ref "PIN3") (pin "9") (pinfunction "9_9") (pintype "passive"))
      (node (ref "U6") (pin "35") (pinfunction "P0.7_35") (pintype "passive"))
    )
    (net (code "75") (name "Net-(U6-P1.0)") (class "Default")
      (node (ref "PIN2") (pin "16") (pinfunction "16_16") (pintype "passive"))
      (node (ref "U6") (pin "3") (pinfunction "P1.0_3") (pintype "passive"))
    )
    (net (code "76") (name "Net-(U6-P1.1)") (class "Default")
      (node (ref "PIN2") (pin "15") (pinfunction "15_15") (pintype "passive"))
      (node (ref "U6") (pin "4") (pinfunction "P1.1_4") (pintype "passive"))
    )
    (net (code "77") (name "Net-(U6-P1.2)") (class "Default")
      (node (ref "PIN2") (pin "14") (pinfunction "14_14") (pintype "passive"))
      (node (ref "U6") (pin "5") (pinfunction "P1.2_5") (pintype "passive"))
    )
    (net (code "78") (name "Net-(U6-P1.3)") (class "Default")
      (node (ref "PIN2") (pin "13") (pinfunction "13_13") (pintype "passive"))
      (node (ref "U6") (pin "6") (pinfunction "P1.3_6") (pintype "passive"))
    )
    (net (code "79") (name "Net-(U6-P1.4)") (class "Default")
      (node (ref "PIN2") (pin "12") (pinfunction "12_12") (pintype "passive"))
      (node (ref "U6") (pin "7") (pinfunction "P1.4_7") (pintype "passive"))
    )
    (net (code "80") (name "Net-(U6-P1.5)") (class "Default")
      (node (ref "PIN2") (pin "11") (pinfunction "11_11") (pintype "passive"))
      (node (ref "U6") (pin "8") (pinfunction "P1.5_8") (pintype "passive"))
    )
    (net (code "81") (name "Net-(U6-P1.6)") (class "Default")
      (node (ref "PIN2") (pin "10") (pinfunction "10_10") (pintype "passive"))
      (node (ref "U6") (pin "9") (pinfunction "P1.6_9") (pintype "passive"))
    )
    (net (code "82") (name "Net-(U6-P1.7)") (class "Default")
      (node (ref "PIN2") (pin "9") (pinfunction "9_9") (pintype "passive"))
      (node (ref "U6") (pin "10") (pinfunction "P1.7_10") (pintype "passive"))
    )
    (net (code "83") (name "Net-(U6-P2.0)") (class "Default")
      (node (ref "PIN3") (pin "1") (pinfunction "1_1") (pintype "passive"))
      (node (ref "U6") (pin "27") (pinfunction "P2.0_27") (pintype "passive"))
    )
    (net (code "84") (name "Net-(U6-P2.1)") (class "Default")
      (node (ref "PIN3") (pin "2") (pinfunction "2_2") (pintype "passive"))
      (node (ref "U6") (pin "28") (pinfunction "P2.1_28") (pintype "passive"))
    )
    (net (code "85") (name "Net-(U6-P2.2)") (class "Default")
      (node (ref "PIN3") (pin "3") (pinfunction "3_3") (pintype "passive"))
      (node (ref "U6") (pin "29") (pinfunction "P2.2_29") (pintype "passive"))
    )
    (net (code "86") (name "Net-(U6-P2.3)") (class "Default")
      (node (ref "PIN3") (pin "4") (pinfunction "4_4") (pintype "passive"))
      (node (ref "U6") (pin "30") (pinfunction "P2.3_30") (pintype "passive"))
    )
    (net (code "87") (name "Net-(U6-P2.4)") (class "Default")
      (node (ref "PIN3") (pin "5") (pinfunction "5_5") (pintype "passive"))
      (node (ref "U6") (pin "31") (pinfunction "P2.4_31") (pintype "passive"))
    )
    (net (code "88") (name "Net-(U6-P2.5)") (class "Default")
      (node (ref "PIN3") (pin "6") (pinfunction "6_6") (pintype "passive"))
      (node (ref "U6") (pin "32") (pinfunction "P2.5_32") (pintype "passive"))
    )
    (net (code "89") (name "Net-(U6-P2.6)") (class "Default")
      (node (ref "PIN3") (pin "7") (pinfunction "7_7") (pintype "passive"))
      (node (ref "U6") (pin "33") (pinfunction "P2.6_33") (pintype "passive"))
    )
    (net (code "90") (name "Net-(U6-P2.7)") (class "Default")
      (node (ref "PIN3") (pin "8") (pinfunction "8_8") (pintype "passive"))
      (node (ref "U6") (pin "34") (pinfunction "P2.7_34") (pintype "passive"))
    )
    (net (code "91") (name "Net-(U6-P3.0)") (class "Default")
      (node (ref "PIN2") (pin "8") (pinfunction "8_8") (pintype "passive"))
      (node (ref "U6") (pin "11") (pinfunction "P3.0_11") (pintype "passive"))
    )
    (net (code "92") (name "Net-(U6-P3.1)") (class "Default")
      (node (ref "PIN2") (pin "7") (pinfunction "7_7") (pintype "passive"))
      (node (ref "U6") (pin "12") (pinfunction "P3.1_12") (pintype "passive"))
    )
    (net (code "93") (name "Net-(U6-P3.2)") (class "Default")
      (node (ref "PIN2") (pin "6") (pinfunction "6_6") (pintype "passive"))
      (node (ref "U6") (pin "13") (pinfunction "P3.2_13") (pintype "passive"))
    )
    (net (code "94") (name "Net-(U6-P3.3)") (class "Default")
      (node (ref "PIN2") (pin "5") (pinfunction "5_5") (pintype "passive"))
      (node (ref "U6") (pin "14") (pinfunction "P3.3_14") (pintype "passive"))
    )
    (net (code "95") (name "Net-(U6-P3.4)") (class "Default")
      (node (ref "PIN2") (pin "4") (pinfunction "4_4") (pintype "passive"))
      (node (ref "U6") (pin "15") (pinfunction "P3.4_15") (pintype "passive"))
    )
    (net (code "96") (name "Net-(U6-P3.5)") (class "Default")
      (node (ref "PIN2") (pin "3") (pinfunction "3_3") (pintype "passive"))
      (node (ref "U6") (pin "16") (pinfunction "P3.5_16") (pintype "passive"))
    )
    (net (code "97") (name "Net-(U6-P3.6)") (class "Default")
      (node (ref "PIN2") (pin "2") (pinfunction "2_2") (pintype "passive"))
      (node (ref "U6") (pin "17") (pinfunction "P3.6_17") (pintype "passive"))
    )
    (net (code "98") (name "Net-(U6-P3.7)") (class "Default")
      (node (ref "PIN2") (pin "1") (pinfunction "1_1") (pintype "passive"))
      (node (ref "U6") (pin "18") (pinfunction "P3.7_18") (pintype "passive"))
    )
    (net (code "99") (name "Net-(U6-P4.0)") (class "Default")
      (node (ref "P12") (pin "1") (pinfunction "1_1") (pintype "passive"))
      (node (ref "U6") (pin "19") (pinfunction "P4.0_19") (pintype "passive"))
    )
    (net (code "100") (name "Net-(U6-P4.1)") (class "Default")
      (node (ref "P12") (pin "2") (pinfunction "2_2") (pintype "passive"))
      (node (ref "U6") (pin "20") (pinfunction "P4.1_20") (pintype "passive"))
    )
    (net (code "101") (name "Net-(U6-P4.2)") (class "Default")
      (node (ref "P12") (pin "3") (pinfunction "3_3") (pintype "passive"))
      (node (ref "U6") (pin "21") (pinfunction "P4.2_21") (pintype "passive"))
    )
    (net (code "102") (name "Net-(U6-P4.3)") (class "Default")
      (node (ref "P12") (pin "4") (pinfunction "4_4") (pintype "passive"))
      (node (ref "U6") (pin "22") (pinfunction "P4.3_22") (pintype "passive"))
    )
    (net (code "103") (name "Net-(U6-P4.4)") (class "Default")
      (node (ref "P12") (pin "5") (pinfunction "5_5") (pintype "passive"))
      (node (ref "U6") (pin "23") (pinfunction "P4.4_23") (pintype "passive"))
    )
    (net (code "104") (name "Net-(U6-P4.5)") (class "Default")
      (node (ref "P12") (pin "6") (pinfunction "6_6") (pintype "passive"))
      (node (ref "U6") (pin "24") (pinfunction "P4.5_24") (pintype "passive"))
    )
    (net (code "105") (name "Net-(U6-P4.6)") (class "Default")
      (node (ref "P12") (pin "7") (pinfunction "7_7") (pintype "passive"))
      (node (ref "U6") (pin "25") (pinfunction "P4.6_25") (pintype "passive"))
    )
    (net (code "106") (name "Net-(U6-P4.7)") (class "Default")
      (node (ref "P12") (pin "8") (pinfunction "8_8") (pintype "passive"))
      (node (ref "U6") (pin "26") (pinfunction "P4.7_26") (pintype "passive"))
    )
    (net (code "107") (name "Net-(U8-OUT1)") (class "Default")
      (node (ref "U8") (pin "16") (pinfunction "OUT1_16") (pintype "passive"))
      (node (ref "xh1") (pin "4") (pinfunction "4_4") (pintype "passive"))
    )
    (net (code "108") (name "Net-(U8-OUT2)") (class "Default")
      (node (ref "U8") (pin "15") (pinfunction "OUT2_15") (pintype "passive"))
      (node (ref "xh1") (pin "3") (pinfunction "3_3") (pintype "passive"))
    )
    (net (code "109") (name "Net-(U8-OUT3)") (class "Default")
      (node (ref "U8") (pin "14") (pinfunction "OUT3_14") (pintype "passive"))
      (node (ref "xh1") (pin "2") (pinfunction "2_2") (pintype "passive"))
    )
    (net (code "110") (name "Net-(U8-OUT4)") (class "Default")
      (node (ref "U8") (pin "13") (pinfunction "OUT4_13") (pintype "passive"))
      (node (ref "xh1") (pin "1") (pinfunction "1_1") (pintype "passive"))
    )
    (net (code "111") (name "Net-(U8-OUT5)") (class "Default")
      (node (ref "BUZZER1") (pin "2") (pinfunction "2_2") (pintype "passive"))
      (node (ref "U8") (pin "12") (pinfunction "OUT5_12") (pintype "passive"))
    )
    (net (code "112") (name "Net-(U11-A0)") (class "Default")
      (node (ref "P13") (pin "3") (pinfunction "3_3") (pintype "passive"))
      (node (ref "U11") (pin "1") (pinfunction "A0_1") (pintype "passive"))
    )
    (net (code "113") (name "Net-(U11-A1)") (class "Default")
      (node (ref "P13") (pin "2") (pinfunction "2_2") (pintype "passive"))
      (node (ref "U11") (pin "2") (pinfunction "A1_2") (pintype "passive"))
    )
    (net (code "114") (name "Net-(U11-A2)") (class "Default")
      (node (ref "P13") (pin "1") (pinfunction "1_1") (pintype "passive"))
      (node (ref "U11") (pin "3") (pinfunction "A2_3") (pintype "passive"))
    )
    (net (code "115") (name "Net-(U11-~{Y}0)") (class "Default")
      (node (ref "LED10") (pin "2") (pinfunction "2_2") (pintype "passive"))
      (node (ref "U11") (pin "15") (pinfunction "~{Y}0_15") (pintype "passive"))
    )
    (net (code "116") (name "Net-(U11-~{Y}1)") (class "Default")
      (node (ref "LED9") (pin "2") (pinfunction "2_2") (pintype "passive"))
      (node (ref "U11") (pin "14") (pinfunction "~{Y}1_14") (pintype "passive"))
    )
    (net (code "117") (name "Net-(U11-~{Y}2)") (class "Default")
      (node (ref "LED8") (pin "2") (pinfunction "2_2") (pintype "passive"))
      (node (ref "U11") (pin "13") (pinfunction "~{Y}2_13") (pintype "passive"))
    )
    (net (code "118") (name "Net-(U11-~{Y}3)") (class "Default")
      (node (ref "LED7") (pin "2") (pinfunction "2_2") (pintype "passive"))
      (node (ref "U11") (pin "12") (pinfunction "~{Y}3_12") (pintype "passive"))
    )
    (net (code "119") (name "Net-(U11-~{Y}4)") (class "Default")
      (node (ref "LED6") (pin "2") (pinfunction "2_2") (pintype "passive"))
      (node (ref "U11") (pin "11") (pinfunction "~{Y}4_11") (pintype "passive"))
    )
    (net (code "120") (name "Net-(U11-~{Y}5)") (class "Default")
      (node (ref "LED5") (pin "2") (pinfunction "2_2") (pintype "passive"))
      (node (ref "U11") (pin "10") (pinfunction "~{Y}5_10") (pintype "passive"))
    )
    (net (code "121") (name "Net-(U11-~{Y}6)") (class "Default")
      (node (ref "LED4") (pin "2") (pinfunction "2_2") (pintype "passive"))
      (node (ref "U11") (pin "9") (pinfunction "~{Y}6_9") (pintype "passive"))
    )
    (net (code "122") (name "Net-(U11-~{Y}7)") (class "Default")
      (node (ref "LED3") (pin "2") (pinfunction "2_2") (pintype "passive"))
      (node (ref "U11") (pin "7") (pinfunction "~{Y}7_7") (pintype "passive"))
    )
    (net (code "123") (name "VCC") (class "Default")
      (node (ref "BUZZER1") (pin "1") (pinfunction "+_1") (pintype "passive"))
      (node (ref "C10") (pin "1") (pinfunction "1_1") (pintype "passive"))
      (node (ref "C11") (pin "1") (pinfunction "1_1") (pintype "passive"))
      (node (ref "C14") (pin "2") (pinfunction "2_2") (pintype "passive"))
      (node (ref "C16") (pin "1") (pinfunction "1_1") (pintype "passive"))
      (node (ref "C17") (pin "1") (pinfunction "1_1") (pintype "passive"))
      (node (ref "C7") (pin "1") (pinfunction "1_1") (pintype "passive"))
      (node (ref "C8") (pin "1") (pinfunction "1_1") (pintype "passive"))
      (node (ref "C9") (pin "1") (pinfunction "1_1") (pintype "passive"))
      (node (ref "OLED1") (pin "2") (pinfunction "VCC_2") (pintype "passive"))
      (node (ref "P11") (pin "1") (pinfunction "1_1") (pintype "passive"))
      (node (ref "P11") (pin "2") (pinfunction "2_2") (pintype "passive"))
      (node (ref "P11") (pin "3") (pinfunction "3_3") (pintype "passive"))
      (node (ref "P11") (pin "4") (pinfunction "4_4") (pintype "passive"))
      (node (ref "PIN3") (pin "17") (pinfunction "17_17") (pintype "passive"))
      (node (ref "PIN3") (pin "18") (pinfunction "18_18") (pintype "passive"))
      (node (ref "PIN4") (pin "17") (pinfunction "17_17") (pintype "passive"))
      (node (ref "PIN4") (pin "18") (pinfunction "18_18") (pintype "passive"))
      (node (ref "R10") (pin "2") (pintype "passive"))
      (node (ref "R11") (pin "2") (pintype "passive"))
      (node (ref "R12") (pin "2") (pintype "passive"))
      (node (ref "R13") (pin "2") (pintype "passive"))
      (node (ref "R14") (pin "1") (pintype "passive"))
      (node (ref "R15") (pin "1") (pintype "passive"))
      (node (ref "R16") (pin "1") (pintype "passive"))
      (node (ref "R17") (pin "1") (pintype "passive"))
      (node (ref "R18") (pin "1") (pintype "passive"))
      (node (ref "R19") (pin "1") (pintype "passive"))
      (node (ref "R20") (pin "1") (pintype "passive"))
      (node (ref "R21") (pin "1") (pintype "passive"))
      (node (ref "R3") (pin "2") (pintype "passive"))
      (node (ref "R4") (pin "2") (pintype "passive"))
      (node (ref "R5") (pin "1") (pintype "passive"))
      (node (ref "R6") (pin "1") (pintype "passive"))
      (node (ref "R9") (pin "2") (pintype "passive"))
      (node (ref "U10") (pin "1") (pinfunction "VDD_1") (pintype "passive"))
      (node (ref "U11") (pin "16") (pinfunction "VCC_16") (pintype "passive"))
      (node (ref "U12") (pin "1") (pinfunction "A0_1") (pintype "passive"))
      (node (ref "U12") (pin "2") (pinfunction "A1_2") (pintype "passive"))
      (node (ref "U12") (pin "3") (pinfunction "A2_3") (pintype "passive"))
      (node (ref "U12") (pin "8") (pinfunction "VCC_8") (pintype "passive"))
      (node (ref "U13") (pin "2") (pinfunction "VCC_2") (pintype "passive"))
      (node (ref "U2") (pin "3") (pinfunction "VIN_3") (pintype "passive"))
      (node (ref "U3") (pin "10") (pinfunction "*SRCLR_10") (pintype "passive"))
      (node (ref "U3") (pin "16") (pinfunction "VCC_16") (pintype "passive"))
      (node (ref "U4") (pin "10") (pinfunction "*SRCLR_10") (pintype "passive"))
      (node (ref "U4") (pin "16") (pinfunction "VCC_16") (pintype "passive"))
      (node (ref "U5") (pin "8") (pinfunction "VCC_8") (pintype "passive"))
      (node (ref "U6") (pin "43") (pinfunction "VCC_43") (pintype "passive"))
      (node (ref "U6") (pin "44") (pinfunction "VCC_44") (pintype "passive"))
      (node (ref "U7") (pin "1") (pinfunction "VCC_1") (pintype "passive"))
      (node (ref "U8") (pin "9") (pinfunction "COM_9") (pintype "passive"))
      (node (ref "U9") (pin "2") (pinfunction "VCC_2") (pintype "passive"))
    )
    (net (code "124") (name "unconnected-(PIN1-Pad7)") (class "Default")
      (node (ref "PIN1") (pin "7") (pinfunction "7_7") (pintype "passive"))
    )
    (net (code "125") (name "unconnected-(PIN1-Pad8)") (class "Default")
      (node (ref "PIN1") (pin "8") (pinfunction "8_8") (pintype "passive"))
    )
    (net (code "126") (name "unconnected-(U3-QH'-Pad9)") (class "Default")
      (node (ref "U3") (pin "9") (pinfunction "QH'_9") (pintype "passive+no_connect"))
    )
    (net (code "127") (name "unconnected-(U4-QE-Pad4)") (class "Default")
      (node (ref "U4") (pin "4") (pinfunction "QE_4") (pintype "passive+no_connect"))
    )
    (net (code "128") (name "unconnected-(U4-QF-Pad5)") (class "Default")
      (node (ref "U4") (pin "5") (pinfunction "QF_5") (pintype "passive+no_connect"))
    )
    (net (code "129") (name "unconnected-(U4-QG-Pad6)") (class "Default")
      (node (ref "U4") (pin "6") (pinfunction "QG_6") (pintype "passive+no_connect"))
    )
    (net (code "130") (name "unconnected-(U4-QH-Pad7)") (class "Default")
      (node (ref "U4") (pin "7") (pinfunction "QH_7") (pintype "passive+no_connect"))
    )
    (net (code "131") (name "unconnected-(U8-IN6-Pad6)") (class "Default")
      (node (ref "U8") (pin "6") (pinfunction "IN6_6") (pintype "passive"))
    )
    (net (code "132") (name "unconnected-(U8-IN7-Pad7)") (class "Default")
      (node (ref "U8") (pin "7") (pinfunction "IN7_7") (pintype "passive"))
    )
    (net (code "133") (name "unconnected-(U8-OUT6-Pad11)") (class "Default")
      (node (ref "U8") (pin "11") (pinfunction "OUT6_11") (pintype "passive"))
    )
    (net (code "134") (name "unconnected-(U8-OUT7-Pad10)") (class "Default")
      (node (ref "U8") (pin "10") (pinfunction "OUT7_10") (pintype "passive"))
    )
    (net (code "135") (name "unconnected-(U10-NC-Pad3)") (class "Default")
      (node (ref "U10") (pin "3") (pinfunction "NC_3") (pintype "passive"))
    )
    (net (code "136") (name "unconnected-(U11-E3-Pad6)") (class "Default")
      (node (ref "U11") (pin "6") (pinfunction "E3_6") (pintype "passive"))
    )
    (net (code "137") (name "unconnected-(U12-GND-Pad4)") (class "Default")
      (node (ref "U12") (pin "4") (pinfunction "GND_4") (pintype "passive"))
    )
    (net (code "138") (name "unconnected-(U13-32KHz-Pad1)") (class "Default")
      (node (ref "U13") (pin "1") (pinfunction "32KHz_1") (pintype "passive"))
    )
    (net (code "139") (name "unconnected-(U13-NC-Pad5)") (class "Default")
      (node (ref "U13") (pin "5") (pinfunction "NC_5") (pintype "passive"))
    )
    (net (code "140") (name "unconnected-(U13-NC-Pad6)") (class "Default")
      (node (ref "U13") (pin "6") (pinfunction "NC_6") (pintype "passive"))
    )
    (net (code "141") (name "unconnected-(U13-NC-Pad7)") (class "Default")
      (node (ref "U13") (pin "7") (pinfunction "NC_7") (pintype "passive"))
    )
    (net (code "142") (name "unconnected-(U13-NC-Pad8)") (class "Default")
      (node (ref "U13") (pin "8") (pinfunction "NC_8") (pintype "passive"))
    )
    (net (code "143") (name "unconnected-(U13-NC-Pad9)") (class "Default")
      (node (ref "U13") (pin "9") (pinfunction "NC_9") (pintype "passive"))
    )
    (net (code "144") (name "unconnected-(U13-NC-Pad10)") (class "Default")
      (node (ref "U13") (pin "10") (pinfunction "NC_10") (pintype "passive"))
    )
    (net (code "145") (name "unconnected-(U13-NC-Pad11)") (class "Default")
      (node (ref "U13") (pin "11") (pinfunction "NC_11") (pintype "passive"))
    )
    (net (code "146") (name "unconnected-(U13-NC-Pad12)") (class "Default")
      (node (ref "U13") (pin "12") (pinfunction "NC_12") (pintype "passive"))
    )
    (net (code "147") (name "unconnected-(U13-~{INT}{slash}SQW-Pad3)") (class "Default")
      (node (ref "U13") (pin "3") (pinfunction "~{INT}/SQW_3") (pintype "passive+no_connect"))
    )
    (net (code "148") (name "unconnected-(U13-~{RST}-Pad4)") (class "Default")
      (node (ref "U13") (pin "4") (pinfunction "~{RST}_4") (pintype "passive+no_connect"))
    )
    (net (code "149") (name "unconnected-(xh1-Pad5)") (class "Default")
      (node (ref "xh1") (pin "5") (pinfunction "5_5") (pintype "passive"))
    )
  )
)
